# Schematic_final.net
KiCad netlist of a schematic drawn in EAGLE
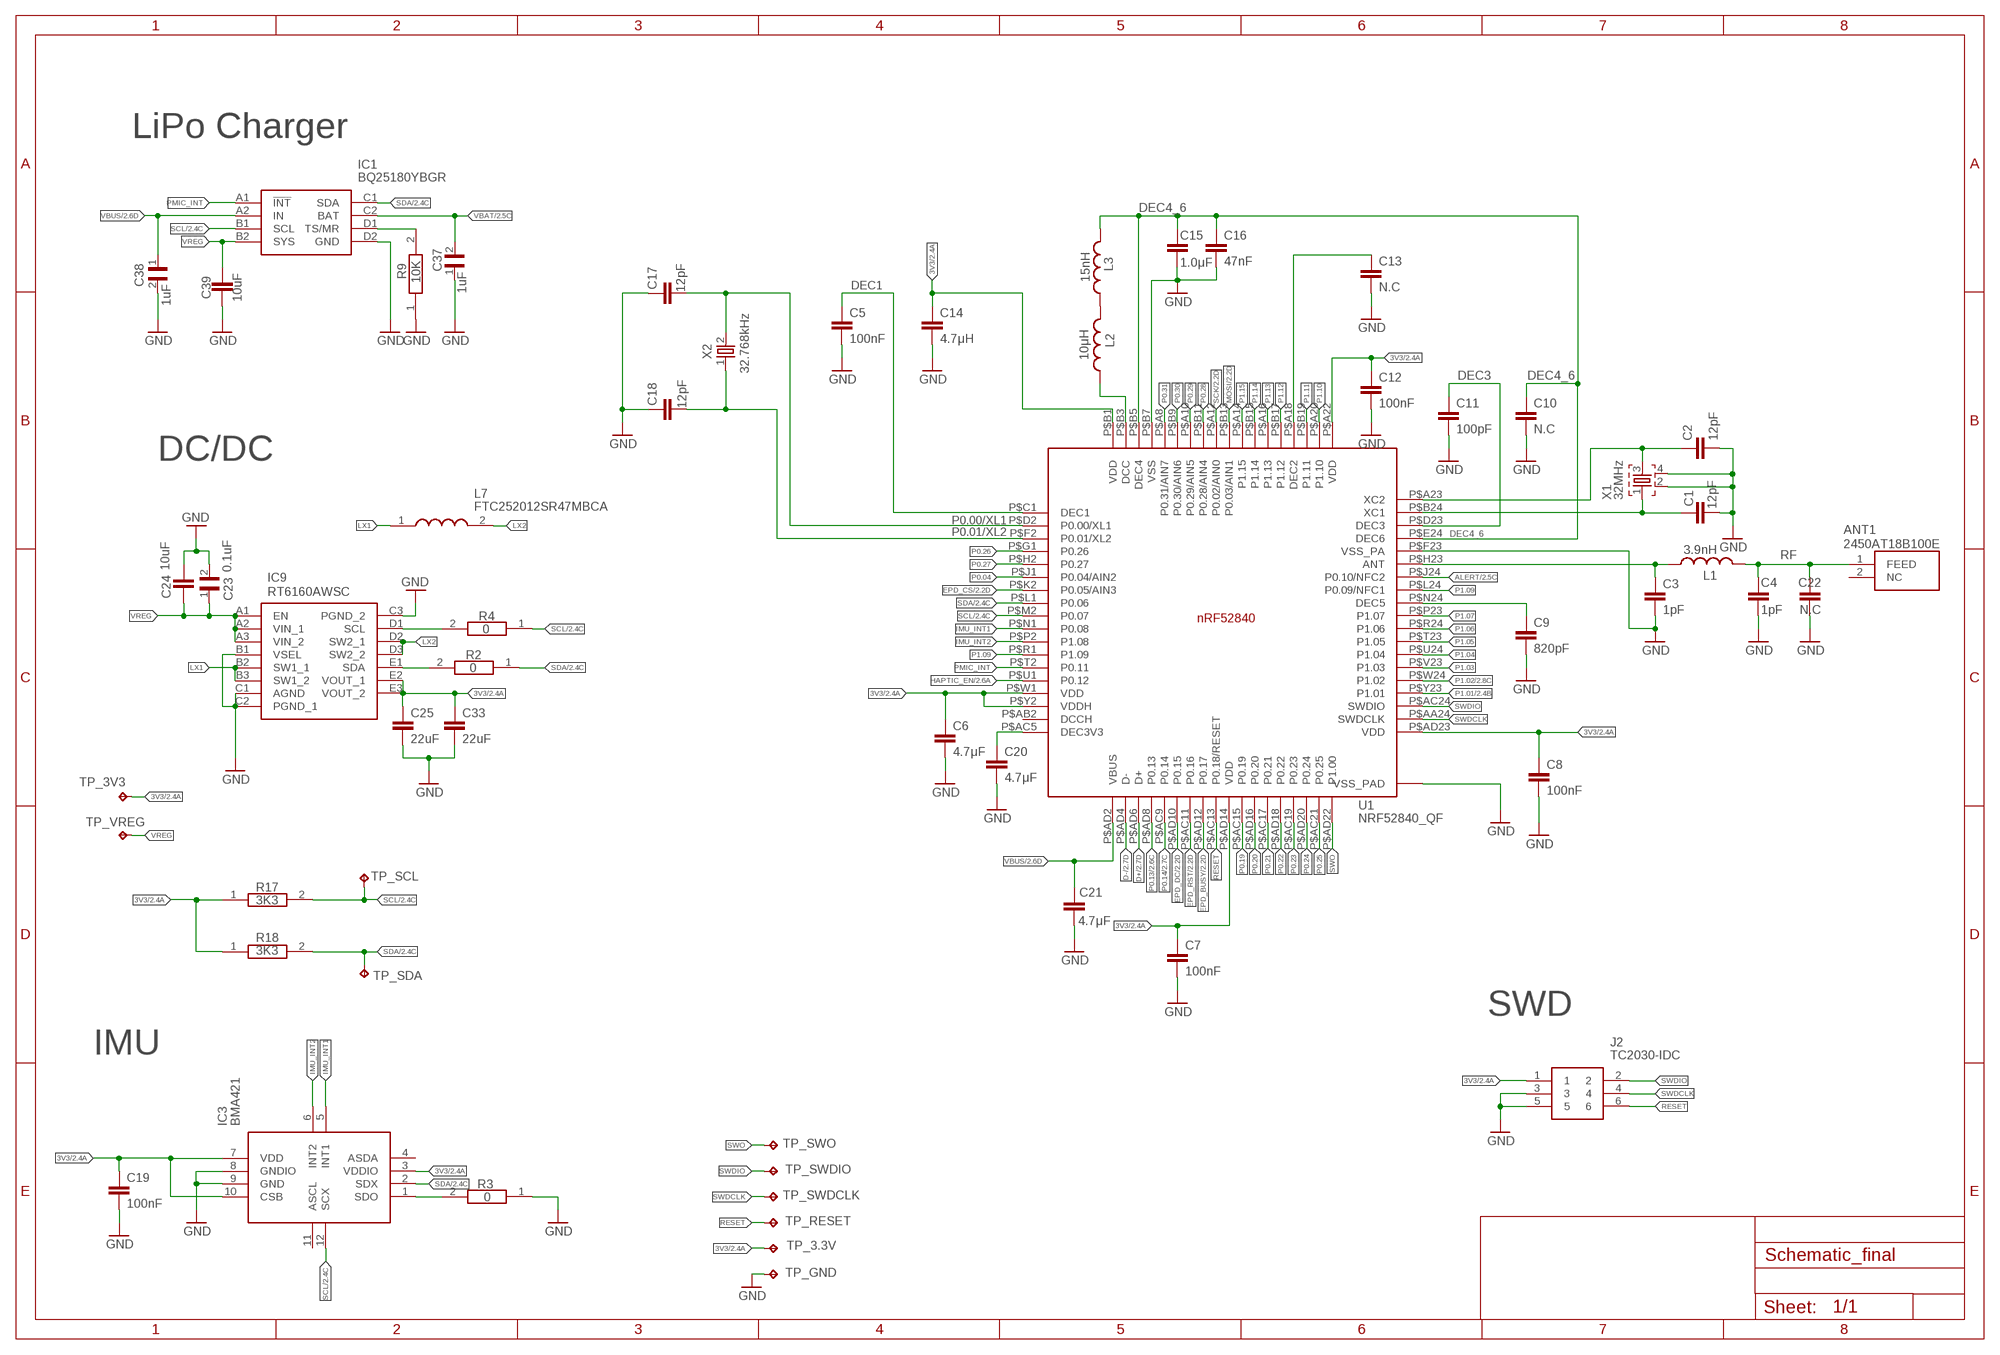
[diagram p0: schematic, sheet 1, part 1 of 2]
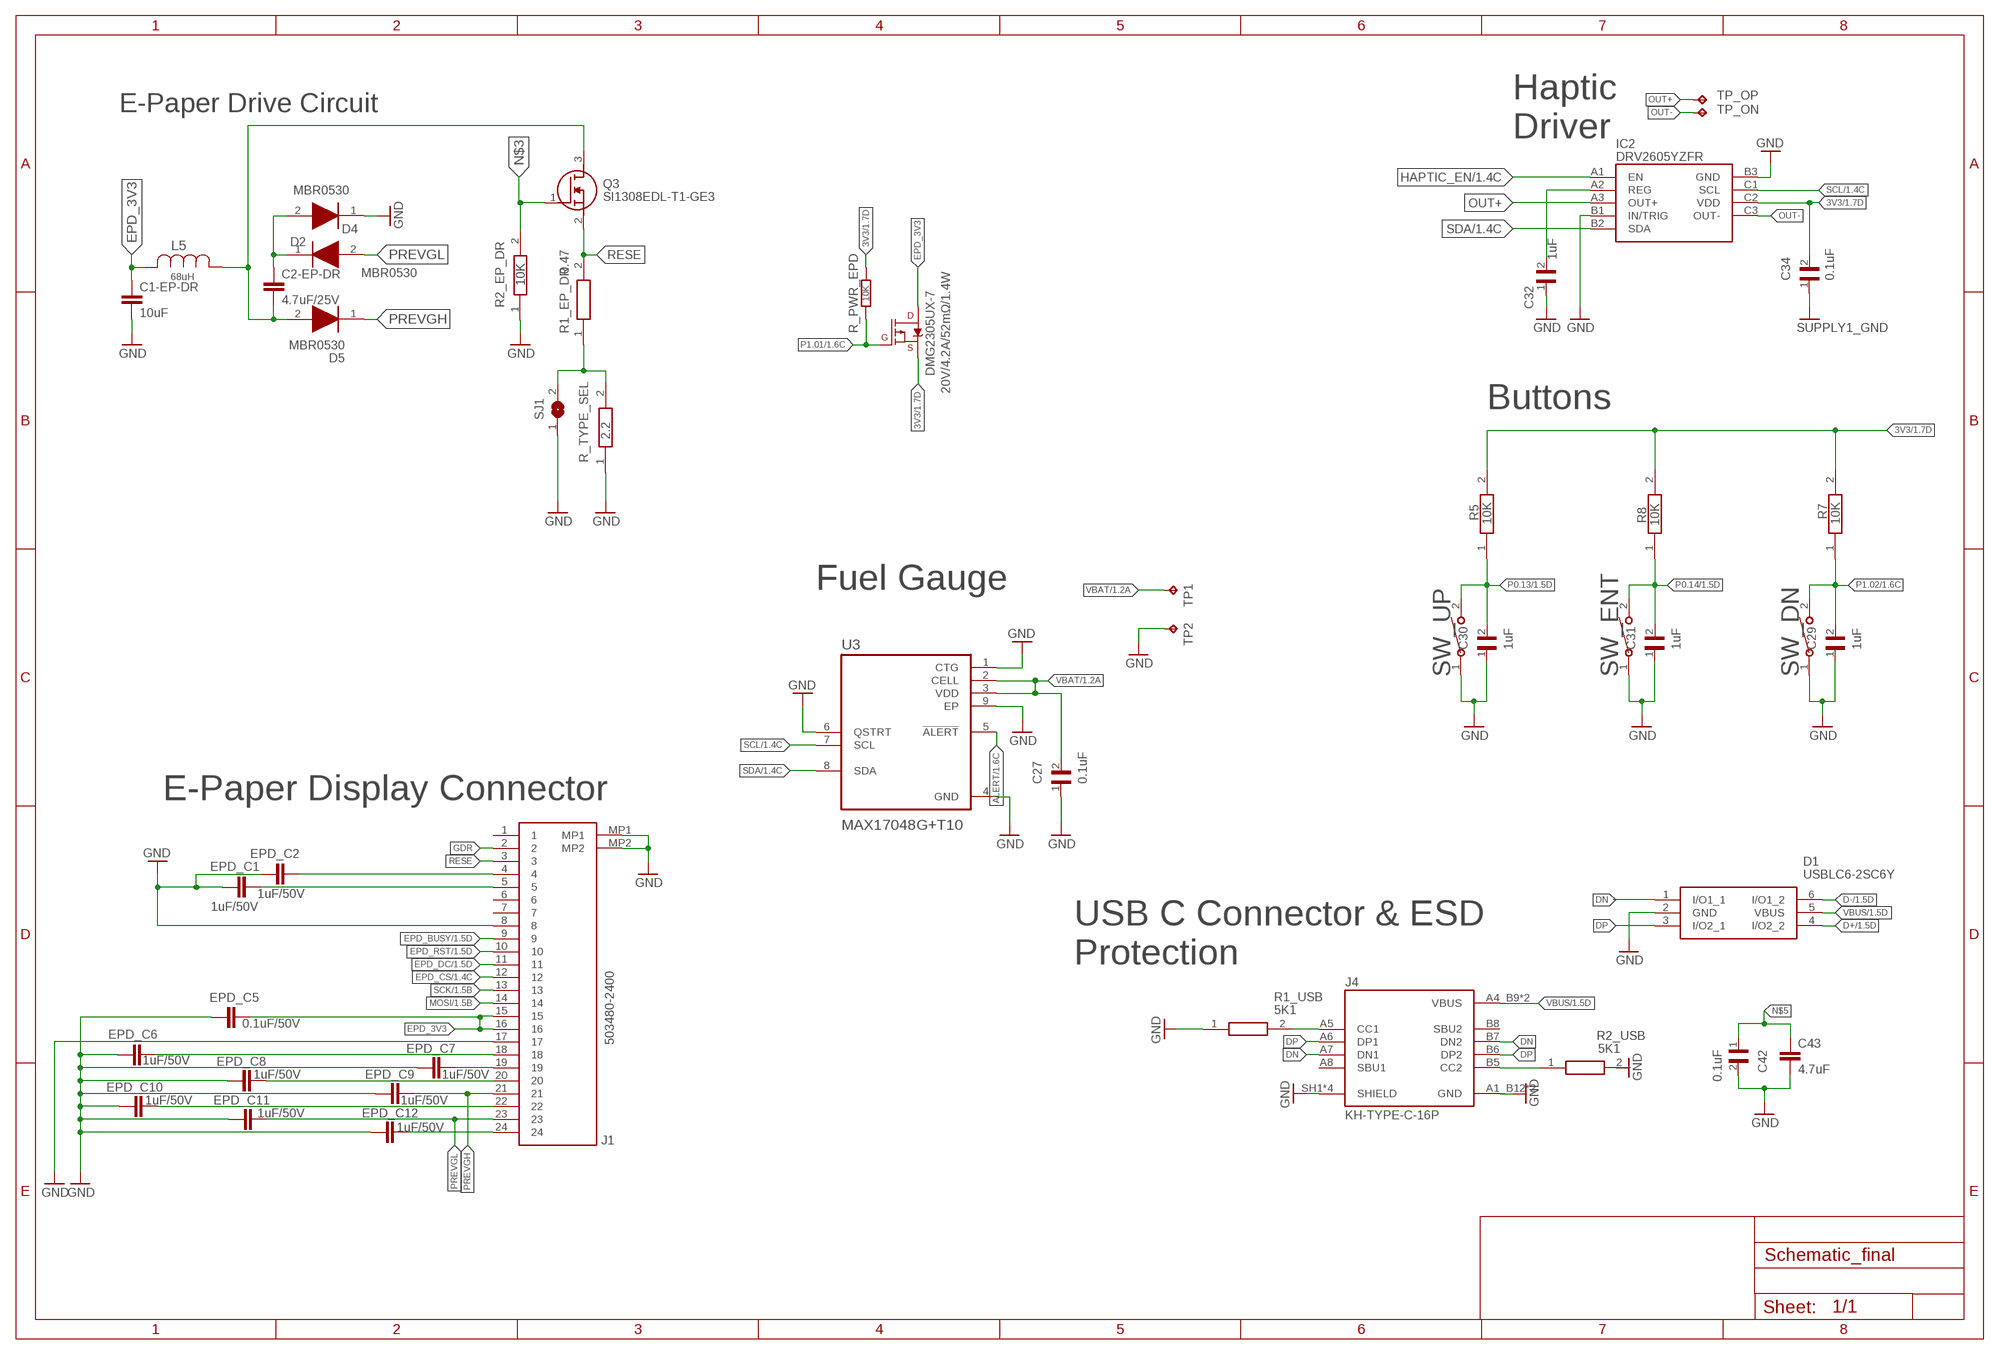
[diagram p1: schematic, sheet 1, part 2 of 2]

(export (version "E")
  (design (tool "Eeschema 10.0.6"))
  (components
    (comp (ref "ANT1")
      (value "2450AT18B100E")
      (footprint "eagle-import:2450AT18B100E_ANTC3216X140N")
      (fields (field (name "MOUSER_PART_NUMBER") "609-2450AT18B100E"))
      (libsource (lib "eagle-import") (part "2450AT18B100E_2450AT18B100E"))
    )
    (comp (ref "C1")
      (value "12pF")
      (footprint "eagle-import:NORDIC_NRF_3_RESC0201_L")
      (libsource (lib "eagle-import") (part "NORDIC_NRF_3_CAPACITOR_0201_L"))
    )
    (comp (ref "C1-EP-DR")
      (value "10uF")
      (footprint "eagle-import:NORDIC_NRF_3_RESC0201_L")
      (libsource (lib "eagle-import") (part "NORDIC_NRF_3_CAPACITOR_0201_L"))
    )
    (comp (ref "C2")
      (value "12pF")
      (footprint "eagle-import:NORDIC_NRF_3_RESC0201_L")
      (libsource (lib "eagle-import") (part "NORDIC_NRF_3_CAPACITOR_0201_L"))
    )
    (comp (ref "C2-EP-DR")
      (value "4.7uF/25V")
      (footprint "eagle-import:NORDIC_NRF_3_RESC0201_L")
      (libsource (lib "eagle-import") (part "NORDIC_NRF_3_CAPACITOR_0201_L"))
    )
    (comp (ref "C3")
      (value "1pF")
      (footprint "eagle-import:NORDIC_NRF_3_RESC0201_L")
      (libsource (lib "eagle-import") (part "NORDIC_NRF_3_CAPACITOR_0201_L"))
    )
    (comp (ref "C4")
      (value "1pF")
      (footprint "eagle-import:NORDIC_NRF_3_RESC0201_L")
      (libsource (lib "eagle-import") (part "NORDIC_NRF_3_CAPACITOR_0201_L"))
    )
    (comp (ref "C5")
      (value "100nF")
      (footprint "eagle-import:NORDIC_NRF_3_RESC0201_L")
      (libsource (lib "eagle-import") (part "NORDIC_NRF_3_CAPACITOR_0201_L"))
    )
    (comp (ref "C6")
      (value "4.7μF")
      (footprint "eagle-import:NORDIC_NRF_3_RESC0201_L")
      (libsource (lib "eagle-import") (part "NORDIC_NRF_3_CAPACITOR_0201_L"))
    )
    (comp (ref "C7")
      (value "100nF")
      (footprint "eagle-import:NORDIC_NRF_3_RESC0201_L")
      (libsource (lib "eagle-import") (part "NORDIC_NRF_3_CAPACITOR_0201_L"))
    )
    (comp (ref "C8")
      (value "100nF")
      (footprint "eagle-import:NORDIC_NRF_3_RESC0201_L")
      (libsource (lib "eagle-import") (part "NORDIC_NRF_3_CAPACITOR_0201_L"))
    )
    (comp (ref "C9")
      (value "820pF")
      (footprint "eagle-import:NORDIC_NRF_3_RESC0201_L")
      (libsource (lib "eagle-import") (part "NORDIC_NRF_3_CAPACITOR_0201_L"))
    )
    (comp (ref "C10")
      (value "N.C")
      (footprint "eagle-import:NORDIC_NRF_3_RESC0201_L")
      (libsource (lib "eagle-import") (part "NORDIC_NRF_3_CAPACITOR_0201_L"))
    )
    (comp (ref "C11")
      (value "100pF")
      (footprint "eagle-import:NORDIC_NRF_3_RESC0201_L")
      (libsource (lib "eagle-import") (part "NORDIC_NRF_3_CAPACITOR_0201_L"))
    )
    (comp (ref "C12")
      (value "100nF")
      (footprint "eagle-import:NORDIC_NRF_3_RESC0201_L")
      (libsource (lib "eagle-import") (part "NORDIC_NRF_3_CAPACITOR_0201_L"))
    )
    (comp (ref "C13")
      (value "N.C")
      (footprint "eagle-import:NORDIC_NRF_3_RESC0201_L")
      (libsource (lib "eagle-import") (part "NORDIC_NRF_3_CAPACITOR_0201_L"))
    )
    (comp (ref "C14")
      (value "4.7μH")
      (footprint "eagle-import:NORDIC_NRF_3_RESC0201_L")
      (libsource (lib "eagle-import") (part "NORDIC_NRF_3_CAPACITOR_0201_L"))
    )
    (comp (ref "C15")
      (value "1.0μF")
      (footprint "eagle-import:NORDIC_NRF_3_RESC0201_L")
      (libsource (lib "eagle-import") (part "NORDIC_NRF_3_CAPACITOR_0201_L"))
    )
    (comp (ref "C16")
      (value "47nF")
      (footprint "eagle-import:NORDIC_NRF_3_RESC0201_L")
      (libsource (lib "eagle-import") (part "NORDIC_NRF_3_CAPACITOR_0201_L"))
    )
    (comp (ref "C17")
      (value "12pF")
      (footprint "eagle-import:NORDIC_NRF_3_RESC0201_L")
      (libsource (lib "eagle-import") (part "NORDIC_NRF_3_CAPACITOR_0201_L"))
    )
    (comp (ref "C18")
      (value "12pF")
      (footprint "eagle-import:NORDIC_NRF_3_RESC0201_L")
      (libsource (lib "eagle-import") (part "NORDIC_NRF_3_CAPACITOR_0201_L"))
    )
    (comp (ref "C19")
      (value "100nF")
      (footprint "eagle-import:NORDIC_NRF_3_RESC0201_L")
      (libsource (lib "eagle-import") (part "NORDIC_NRF_3_CAPACITOR_0201_L"))
    )
    (comp (ref "C20")
      (value "4.7μF")
      (footprint "eagle-import:NORDIC_NRF_3_RESC0201_L")
      (libsource (lib "eagle-import") (part "NORDIC_NRF_3_CAPACITOR_0201_L"))
    )
    (comp (ref "C21")
      (value "4.7μF")
      (footprint "eagle-import:NORDIC_NRF_3_RESC0201_L")
      (libsource (lib "eagle-import") (part "NORDIC_NRF_3_CAPACITOR_0201_L"))
    )
    (comp (ref "C22")
      (value "N.C")
      (footprint "eagle-import:NORDIC_NRF_3_RESC0201_L")
      (libsource (lib "eagle-import") (part "NORDIC_NRF_3_CAPACITOR_0201_L"))
    )
    (comp (ref "C23")
      (value "0.1uF")
      (footprint "eagle-import:GRM011R60J152KE01L_2_CAPC0201X13N")
      (fields (field (name "MF") "Murata") (field (name "MP") "GRM011R60J152KE01L"))
      (libsource (lib "eagle-import") (part "GRM011R60J152KE01L_2_GRM011R60J152KE01L"))
    )
    (comp (ref "C24")
      (value "10uF")
      (footprint "eagle-import:NORDIC_NRF_3_RESC0201_L")
      (libsource (lib "eagle-import") (part "NORDIC_NRF_3_CAPACITOR_0201_L"))
    )
    (comp (ref "C25")
      (value "22uF")
      (footprint "eagle-import:NORDIC_NRF_3_RESC0201_L")
      (libsource (lib "eagle-import") (part "NORDIC_NRF_3_CAPACITOR_0201_L"))
    )
    (comp (ref "C27")
      (value "0.1uF")
      (footprint "eagle-import:GRM011R60J152KE01L_2_CAPC0201X13N")
      (fields (field (name "MF") "Murata") (field (name "MP") "GRM011R60J152KE01L"))
      (libsource (lib "eagle-import") (part "GRM011R60J152KE01L_2_GRM011R60J152KE01L"))
    )
    (comp (ref "C29")
      (value "1uF")
      (footprint "eagle-import:GRM011R60J152KE01L_2_CAPC0201X13N")
      (fields (field (name "MF") "Murata") (field (name "MP") "GRM011R60J152KE01L"))
      (libsource (lib "eagle-import") (part "GRM011R60J152KE01L_2_GRM011R60J152KE01L"))
    )
    (comp (ref "C30")
      (value "1uF")
      (footprint "eagle-import:GRM011R60J152KE01L_2_CAPC0201X13N")
      (fields (field (name "MF") "Murata") (field (name "MP") "GRM011R60J152KE01L"))
      (libsource (lib "eagle-import") (part "GRM011R60J152KE01L_2_GRM011R60J152KE01L"))
    )
    (comp (ref "C31")
      (value "1uF")
      (footprint "eagle-import:GRM011R60J152KE01L_2_CAPC0201X13N")
      (fields (field (name "MF") "Murata") (field (name "MP") "GRM011R60J152KE01L"))
      (libsource (lib "eagle-import") (part "GRM011R60J152KE01L_2_GRM011R60J152KE01L"))
    )
    (comp (ref "C32")
      (value "1uF")
      (footprint "eagle-import:GRM011R60J152KE01L_2_CAPC0201X13N")
      (fields (field (name "MF") "Murata") (field (name "MP") "GRM011R60J152KE01L"))
      (libsource (lib "eagle-import") (part "GRM011R60J152KE01L_2_GRM011R60J152KE01L"))
    )
    (comp (ref "C33")
      (value "22uF")
      (footprint "eagle-import:NORDIC_NRF_3_RESC0201_L")
      (libsource (lib "eagle-import") (part "NORDIC_NRF_3_CAPACITOR_0201_L"))
    )
    (comp (ref "C34")
      (value "0.1uF")
      (footprint "eagle-import:GRM011R60J152KE01L_2_CAPC0201X13N")
      (fields (field (name "MF") "Murata") (field (name "MP") "GRM011R60J152KE01L"))
      (libsource (lib "eagle-import") (part "GRM011R60J152KE01L_2_GRM011R60J152KE01L"))
    )
    (comp (ref "C37")
      (value "1uF")
      (footprint "eagle-import:GRM011R60J152KE01L_2_CAPC0201X13N")
      (fields (field (name "MF") "Murata") (field (name "MP") "GRM011R60J152KE01L"))
      (libsource (lib "eagle-import") (part "GRM011R60J152KE01L_2_GRM011R60J152KE01L"))
    )
    (comp (ref "C38")
      (value "1uF")
      (footprint "eagle-import:GRM011R60J152KE01L_2_CAPC0201X13N")
      (fields (field (name "MF") "Murata") (field (name "MP") "GRM011R60J152KE01L"))
      (libsource (lib "eagle-import") (part "GRM011R60J152KE01L_2_GRM011R60J152KE01L"))
    )
    (comp (ref "C39")
      (value "10uF")
      (footprint "eagle-import:NORDIC_NRF_3_RESC0201_L")
      (libsource (lib "eagle-import") (part "NORDIC_NRF_3_CAPACITOR_0201_L"))
    )
    (comp (ref "C42")
      (value "0.1uF")
      (footprint "eagle-import:GRM011R60J152KE01L_2_CAPC0201X13N")
      (fields (field (name "MF") "Murata") (field (name "MP") "GRM011R60J152KE01L"))
      (libsource (lib "eagle-import") (part "GRM011R60J152KE01L_2_GRM011R60J152KE01L"))
    )
    (comp (ref "C43")
      (value "4.7uF")
      (footprint "eagle-import:NORDIC_NRF_3_RESC0201_L")
      (libsource (lib "eagle-import") (part "NORDIC_NRF_3_CAPACITOR_0201_L"))
    )
    (comp (ref "D1")
      (value "USBLC6-2SC6Y")
      (footprint "eagle-import:ESP32_C6_LIBRARY_3_SOT95P280X145-6N")
      (fields (field (name "MF") "STMicroelectronics"))
      (libsource (lib "eagle-import") (part "ESP32_C6_LIBRARY_3_USBLC6-2SC6Y"))
    )
    (comp (ref "D2")
      (value "MBR0530")
      (footprint "eagle-import:ESP32_C6_LIBRARY_5_SOD3716X135N")
      (fields (field (name "MF") "ON Semiconductor"))
      (libsource (lib "eagle-import") (part "ESP32_C6_LIBRARY_5_MBR0530"))
    )
    (comp (ref "D4")
      (value "MBR0530")
      (footprint "eagle-import:ESP32_C6_LIBRARY_5_SOD3716X135N")
      (fields (field (name "MF") "ON Semiconductor"))
      (libsource (lib "eagle-import") (part "ESP32_C6_LIBRARY_5_MBR0530"))
    )
    (comp (ref "D5")
      (value "MBR0530")
      (footprint "eagle-import:ESP32_C6_LIBRARY_5_SOD3716X135N")
      (fields (field (name "MF") "ON Semiconductor"))
      (libsource (lib "eagle-import") (part "ESP32_C6_LIBRARY_5_MBR0530"))
    )
    (comp (ref "DMG2305UX-7")
      (value "20V/4.2A/52mΩ/1.4W")
      (footprint "eagle-import:ESP32_C6_LIBRARY_4_ESP32_C6_LIBRARY_4_ESP32_C6_LIBRARY_4_ESP32_C6_LIBRARY_4_ESP32_WROVER_SPARKFUN-DISCRETESEMI_SOT23-3")
      (libsource (lib "eagle-import") (part "ESP32_C6_LIBRARY_4_ESP32_WROVER_SPARKFUN-DISCRETESEMI_MOSFET_PCH-DMG2305UX-7"))
    )
    (comp (ref "EPD_C1")
      (value "1uF/50V")
      (footprint "eagle-import:NORDIC_NRF_3_RESC0201_L")
      (libsource (lib "eagle-import") (part "NORDIC_NRF_3_CAPACITOR_0201_L"))
    )
    (comp (ref "EPD_C2")
      (value "1uF/50V")
      (footprint "eagle-import:NORDIC_NRF_3_RESC0201_L")
      (libsource (lib "eagle-import") (part "NORDIC_NRF_3_CAPACITOR_0201_L"))
    )
    (comp (ref "EPD_C5")
      (value "0.1uF/50V")
      (footprint "eagle-import:NORDIC_NRF_3_RESC0201_L")
      (libsource (lib "eagle-import") (part "NORDIC_NRF_3_CAPACITOR_0201_L"))
    )
    (comp (ref "EPD_C6")
      (value "1uF/50V")
      (footprint "eagle-import:NORDIC_NRF_3_RESC0201_L")
      (libsource (lib "eagle-import") (part "NORDIC_NRF_3_CAPACITOR_0201_L"))
    )
    (comp (ref "EPD_C7")
      (value "1uF/50V")
      (footprint "eagle-import:NORDIC_NRF_3_RESC0201_L")
      (libsource (lib "eagle-import") (part "NORDIC_NRF_3_CAPACITOR_0201_L"))
    )
    (comp (ref "EPD_C8")
      (value "1uF/50V")
      (footprint "eagle-import:NORDIC_NRF_3_RESC0201_L")
      (libsource (lib "eagle-import") (part "NORDIC_NRF_3_CAPACITOR_0201_L"))
    )
    (comp (ref "EPD_C9")
      (value "1uF/50V")
      (footprint "eagle-import:NORDIC_NRF_3_RESC0201_L")
      (libsource (lib "eagle-import") (part "NORDIC_NRF_3_CAPACITOR_0201_L"))
    )
    (comp (ref "EPD_C10")
      (value "1uF/50V")
      (footprint "eagle-import:NORDIC_NRF_3_RESC0201_L")
      (libsource (lib "eagle-import") (part "NORDIC_NRF_3_CAPACITOR_0201_L"))
    )
    (comp (ref "EPD_C11")
      (value "1uF/50V")
      (footprint "eagle-import:NORDIC_NRF_3_RESC0201_L")
      (libsource (lib "eagle-import") (part "NORDIC_NRF_3_CAPACITOR_0201_L"))
    )
    (comp (ref "EPD_C12")
      (value "1uF/50V")
      (footprint "eagle-import:NORDIC_NRF_3_RESC0201_L")
      (libsource (lib "eagle-import") (part "NORDIC_NRF_3_CAPACITOR_0201_L"))
    )
    (comp (ref "IC1")
      (value "BQ25180YBGR")
      (footprint "eagle-import:BQ25180YBGR_BGA8C40P2X4_100X155X50")
      (fields (field (name "MOUSER_PART_NUMBER") "595-BQ25180YBGR"))
      (libsource (lib "eagle-import") (part "BQ25180YBGR_BQ25180YBGR"))
    )
    (comp (ref "IC2")
      (value "DRV2605YZFR")
      (footprint "eagle-import:DRV2605YZFR_BGA9C50P3X3_144X144X62")
      (libsource (lib "eagle-import") (part "DRV2605YZFR_DRV2605YZFR"))
    )
    (comp (ref "IC3")
      (value "BMA421")
      (footprint "eagle-import:BMA423_BMA423")
      (fields
        (field (name "MANUFACTURER_PART_NUMBER") "BMA423")
        (field (name "MOUSER_PART_NUMBER") "262-BMA423")
      )
      (libsource (lib "eagle-import") (part "BMA423_BMA423"))
    )
    (comp (ref "IC9")
      (value "RT6160AWSC")
      (footprint "eagle-import:RT6160AWSC_BGA15C40P3X5_140X230X60")
      (fields (field (name "MOUSER_PART_NUMBER") "835-RT6160AWSC"))
      (libsource (lib "eagle-import") (part "RT6160AWSC_RT6160AWSC"))
    )
    (comp (ref "J1")
      (value "503480-2400")
      (footprint "eagle-import:503480-2400_5034802400")
      (fields (field (name "MOUSER_PART_NUMBER") "538-503480-2400"))
      (libsource (lib "eagle-import") (part "503480-2400_503480-2400"))
    )
    (comp (ref "J2")
      (value "TC2030-IDC")
      (footprint "eagle-import:TC2030-IDC_TC2030IDC")
      (libsource (lib "eagle-import") (part "TC2030-IDC_TC2030-IDC"))
    )
    (comp (ref "J4")
      (value "KH-TYPE-C-16P")
      (footprint "eagle-import:KH-TYPE-C-16P_KINGHELM_KH-TYPE-C-16P")
      (fields (field (name "MF") "kinghelm"))
      (libsource (lib "eagle-import") (part "KH-TYPE-C-16P_KH-TYPE-C-16P"))
    )
    (comp (ref "L1")
      (value "3.9nH")
      (footprint "eagle-import:NORDIC_NRF_2_RESC0402_L")
      (libsource (lib "eagle-import") (part "NORDIC_NRF_2_INDUCTOR_0402_L"))
    )
    (comp (ref "L2")
      (value "10μH")
      (footprint "eagle-import:NORDIC_NRF_2_RESC0402_L")
      (libsource (lib "eagle-import") (part "NORDIC_NRF_2_INDUCTOR_0402_L"))
    )
    (comp (ref "L3")
      (value "15nH")
      (footprint "eagle-import:NORDIC_NRF_2_RESC0402_L")
      (libsource (lib "eagle-import") (part "NORDIC_NRF_2_INDUCTOR_0402_L"))
    )
    (comp (ref "L5")
      (value "68uH")
      (footprint "eagle-import:ESP32_C6_LIBRARY_2_IND_4828-WE-TPC_WRE")
      (fields
        (field (name "MANUFACTURER_PART_NUMBER") "744043680")
        (field (name "COPYRIGHT") "Copyright (C) 2024 Ultra Librarian. All rights reserved.")
      )
      (libsource (lib "eagle-import") (part "ESP32_C6_LIBRARY_2_744043680IND_4828-WE-TPC_WRE"))
    )
    (comp (ref "L7")
      (value "FTC252012SR47MBCA")
      (footprint "eagle-import:MLP2016SR47MT0S1_INDC2016X100N")
      (libsource (lib "eagle-import") (part "MLP2016SR47MT0S1_FTC252012SR47MBCA"))
    )
    (comp (ref "Q3")
      (value "SI1308EDL-T1-GE3")
      (footprint "eagle-import:ESP32_C6_LIBRARY_6_SOT65P210X110-3N")
      (fields (field (name "MF") "Vishay Siliconix"))
      (libsource (lib "eagle-import") (part "ESP32_C6_LIBRARY_6_SI1308EDL-T1-GE3"))
    )
    (comp (ref "R1_EP_DR")
      (value "0.47")
      (footprint "eagle-import:CPF0201D7K68C1_0201")
      (libsource (lib "eagle-import") (part "CPF0201D7K68C1_CPF0201D7K68C1"))
    )
    (comp (ref "R1_USB")
      (value "5K1")
      (footprint "eagle-import:CPF0201D7K68C1_0201")
      (libsource (lib "eagle-import") (part "CPF0201D7K68C1_CPF0201D7K68C1"))
    )
    (comp (ref "R2")
      (value "0")
      (footprint "eagle-import:CPF0201D7K68C1_0201")
      (libsource (lib "eagle-import") (part "CPF0201D7K68C1_CPF0201D7K68C1"))
    )
    (comp (ref "R2_EP_DR")
      (value "10K")
      (footprint "eagle-import:CPF0201D7K68C1_0201")
      (libsource (lib "eagle-import") (part "CPF0201D7K68C1_CPF0201D7K68C1"))
    )
    (comp (ref "R2_USB")
      (value "5K1")
      (footprint "eagle-import:CPF0201D7K68C1_0201")
      (libsource (lib "eagle-import") (part "CPF0201D7K68C1_CPF0201D7K68C1"))
    )
    (comp (ref "R3")
      (value "0")
      (footprint "eagle-import:CPF0201D7K68C1_0201")
      (libsource (lib "eagle-import") (part "CPF0201D7K68C1_CPF0201D7K68C1"))
    )
    (comp (ref "R4")
      (value "0")
      (footprint "eagle-import:CPF0201D7K68C1_0201")
      (libsource (lib "eagle-import") (part "CPF0201D7K68C1_CPF0201D7K68C1"))
    )
    (comp (ref "R5")
      (value "10K")
      (footprint "eagle-import:CPF0201D7K68C1_0201")
      (libsource (lib "eagle-import") (part "CPF0201D7K68C1_CPF0201D7K68C1"))
    )
    (comp (ref "R7")
      (value "10K")
      (footprint "eagle-import:CPF0201D7K68C1_0201")
      (libsource (lib "eagle-import") (part "CPF0201D7K68C1_CPF0201D7K68C1"))
    )
    (comp (ref "R8")
      (value "10K")
      (footprint "eagle-import:CPF0201D7K68C1_0201")
      (libsource (lib "eagle-import") (part "CPF0201D7K68C1_CPF0201D7K68C1"))
    )
    (comp (ref "R9")
      (value "10K")
      (footprint "eagle-import:CPF0201D7K68C1_0201")
      (libsource (lib "eagle-import") (part "CPF0201D7K68C1_CPF0201D7K68C1"))
    )
    (comp (ref "R17")
      (value "3K3")
      (footprint "eagle-import:CPF0201D7K68C1_0201")
      (libsource (lib "eagle-import") (part "CPF0201D7K68C1_CPF0201D7K68C1"))
    )
    (comp (ref "R18")
      (value "3K3")
      (footprint "eagle-import:CPF0201D7K68C1_0201")
      (libsource (lib "eagle-import") (part "CPF0201D7K68C1_CPF0201D7K68C1"))
    )
    (comp (ref "R_PWR_EPD")
      (value "10K")
      (footprint "eagle-import:RESC1005X40")
      (libsource (lib "eagle-import") (part "RESISTOR_CHIP-0402(1005-METRIC)_"))
    )
    (comp (ref "R_TYPE_SEL")
      (value "2.2")
      (footprint "eagle-import:CPF0201D7K68C1_0201")
      (libsource (lib "eagle-import") (part "CPF0201D7K68C1_CPF0201D7K68C1"))
    )
    (comp (ref "SJ1")
      (value "ESP32_C6_LIBRARY_7_JUMPER_SJ")
      (footprint "eagle-import:ESP32_C6_LIBRARY_7_JUMPER_SJ")
      (libsource (lib "eagle-import") (part "ESP32_C6_LIBRARY_7_JUMPER_SJ"))
    )
    (comp (ref "SW_DN")
      (value "2025-10-22_07-23-44_LIBRARY_EVP-AKE31ASW_EVP-AKE31A_PAN")
      (footprint "eagle-import:2025-10-22_07-23-44_LIBRARY_SW_EVP-AKE31A_PAN")
      (fields
        (field (name "MANUFACTURER_PART_NUMBER") "EVP-AKE31A")
        (field (name "COPYRIGHT") "Copyright (C) 2025 Ultra Librarian. All rights reserved.")
      )
      (libsource (lib "eagle-import") (part "2025-10-22_07-23-44_LIBRARY_EVP-AKE31ASW_EVP-AKE31A_PAN"))
    )
    (comp (ref "SW_ENT")
      (value "2025-10-22_07-23-44_LIBRARY_EVP-AKE31ASW_EVP-AKE31A_PAN")
      (footprint "eagle-import:2025-10-22_07-23-44_LIBRARY_SW_EVP-AKE31A_PAN")
      (fields
        (field (name "MANUFACTURER_PART_NUMBER") "EVP-AKE31A")
        (field (name "COPYRIGHT") "Copyright (C) 2025 Ultra Librarian. All rights reserved.")
      )
      (libsource (lib "eagle-import") (part "2025-10-22_07-23-44_LIBRARY_EVP-AKE31ASW_EVP-AKE31A_PAN"))
    )
    (comp (ref "SW_UP")
      (value "2025-10-22_07-23-44_LIBRARY_EVP-AKE31ASW_EVP-AKE31A_PAN")
      (footprint "eagle-import:2025-10-22_07-23-44_LIBRARY_SW_EVP-AKE31A_PAN")
      (fields
        (field (name "MANUFACTURER_PART_NUMBER") "EVP-AKE31A")
        (field (name "COPYRIGHT") "Copyright (C) 2025 Ultra Librarian. All rights reserved.")
      )
      (libsource (lib "eagle-import") (part "2025-10-22_07-23-44_LIBRARY_EVP-AKE31ASW_EVP-AKE31A_PAN"))
    )
    (comp (ref "TP1")
      (value "HECTOR_WATCH_1_TPTP20R")
      (footprint "eagle-import:HECTOR_WATCH_1_TP20R")
      (libsource (lib "eagle-import") (part "HECTOR_WATCH_1_TPTP20R"))
    )
    (comp (ref "TP2")
      (value "HECTOR_WATCH_1_TPTP20R")
      (footprint "eagle-import:HECTOR_WATCH_1_TP20R")
      (libsource (lib "eagle-import") (part "HECTOR_WATCH_1_TPTP20R"))
    )
    (comp (ref "TP_3.3V")
      (value "HECTOR_WATCH_1_TPTP20R")
      (footprint "eagle-import:HECTOR_WATCH_1_TP20R")
      (libsource (lib "eagle-import") (part "HECTOR_WATCH_1_TPTP20R"))
    )
    (comp (ref "TP_3V3")
      (value "HECTOR_WATCH_1_TPTP20R")
      (footprint "eagle-import:HECTOR_WATCH_1_TP20R")
      (libsource (lib "eagle-import") (part "HECTOR_WATCH_1_TPTP20R"))
    )
    (comp (ref "TP_GND")
      (value "HECTOR_WATCH_1_TPTP20R")
      (footprint "eagle-import:HECTOR_WATCH_1_TP20R")
      (libsource (lib "eagle-import") (part "HECTOR_WATCH_1_TPTP20R"))
    )
    (comp (ref "TP_ON")
      (value "HECTOR_WATCH_1_TPTP20R")
      (footprint "eagle-import:HECTOR_WATCH_1_TP20R")
      (libsource (lib "eagle-import") (part "HECTOR_WATCH_1_TPTP20R"))
    )
    (comp (ref "TP_OP")
      (value "TP_OP")
      (footprint "eagle-import:HECTOR_WATCH_1_TP20R")
      (libsource (lib "eagle-import") (part "HECTOR_WATCH_1_TPTP20R"))
    )
    (comp (ref "TP_RESET")
      (value "HECTOR_WATCH_1_TPTP20R")
      (footprint "eagle-import:HECTOR_WATCH_1_TP20R")
      (libsource (lib "eagle-import") (part "HECTOR_WATCH_1_TPTP20R"))
    )
    (comp (ref "TP_SCL")
      (value "HECTOR_WATCH_1_TPTP20R")
      (footprint "eagle-import:HECTOR_WATCH_1_TP20R")
      (libsource (lib "eagle-import") (part "HECTOR_WATCH_1_TPTP20R"))
    )
    (comp (ref "TP_SDA")
      (value "HECTOR_WATCH_1_TPTP20R")
      (footprint "eagle-import:HECTOR_WATCH_1_TP20R")
      (libsource (lib "eagle-import") (part "HECTOR_WATCH_1_TPTP20R"))
    )
    (comp (ref "TP_SWDCLK")
      (value "HECTOR_WATCH_1_TPTP20R")
      (footprint "eagle-import:HECTOR_WATCH_1_TP20R")
      (libsource (lib "eagle-import") (part "HECTOR_WATCH_1_TPTP20R"))
    )
    (comp (ref "TP_SWDIO")
      (value "HECTOR_WATCH_1_TPTP20R")
      (footprint "eagle-import:HECTOR_WATCH_1_TP20R")
      (libsource (lib "eagle-import") (part "HECTOR_WATCH_1_TPTP20R"))
    )
    (comp (ref "TP_SWO")
      (value "HECTOR_WATCH_1_TPTP20R")
      (footprint "eagle-import:HECTOR_WATCH_1_TP20R")
      (libsource (lib "eagle-import") (part "HECTOR_WATCH_1_TPTP20R"))
    )
    (comp (ref "TP_VREG")
      (value "HECTOR_WATCH_1_TPTP20R")
      (footprint "eagle-import:HECTOR_WATCH_1_TP20R")
      (libsource (lib "eagle-import") (part "HECTOR_WATCH_1_TPTP20R"))
    )
    (comp (ref "U1")
      (value "NRF52840_QF")
      (footprint "eagle-import:NORDIC_NRF_4_AQFN50P700X700X85_HS-74N")
      (libsource (lib "eagle-import") (part "NORDIC_NRF_4_NRF52840_QF"))
    )
    (comp (ref "U3")
      (value "MAX17048G+T10")
      (footprint "eagle-import:ESP32_C6_LIBRARY_SON50P200X200X80-9N")
      (fields (field (name "MF") "Analog Devices"))
      (libsource (lib "eagle-import") (part "ESP32_C6_LIBRARY_MAX17048G+T10"))
    )
    (comp (ref "X1")
      (value "32MHz")
      (footprint "eagle-import:NORDIC_NRF_BT-XTAL_2016_N")
      (libsource (lib "eagle-import") (part "NORDIC_NRF_XTAL_32MHZ"))
    )
    (comp (ref "X2")
      (value "32.768kHz")
      (footprint "eagle-import:NORDIC_NRF_1_XTAL_3215_N")
      (libsource (lib "eagle-import") (part "NORDIC_NRF_1_XTAL_32KHZ"))
    )
  )
  (nets
    (net (code "1") (name "/DEC1") (class "Default")
      (node (ref "C5") (pin "1") (pinfunction "1_1") (pintype "passive"))
      (node (ref "U1") (pin "P$C1") (pinfunction "DEC1_P$C1") (pintype "power_in"))
    )
    (net (code "2") (name "/DEC3") (class "Default")
      (node (ref "C11") (pin "1") (pinfunction "1_1") (pintype "passive"))
      (node (ref "U1") (pin "P$D23") (pinfunction "DEC3_P$D23") (pintype "bidirectional"))
    )
    (net (code "3") (name "/DEC4_6") (class "Default")
      (node (ref "C10") (pin "1") (pinfunction "1_1") (pintype "passive"))
      (node (ref "C15") (pin "1") (pinfunction "1_1") (pintype "passive"))
      (node (ref "C16") (pin "1") (pinfunction "1_1") (pintype "passive"))
      (node (ref "L3") (pin "2") (pinfunction "2_2") (pintype "passive"))
      (node (ref "U1") (pin "P$B5") (pinfunction "DEC4_P$B5") (pintype "power_in"))
      (node (ref "U1") (pin "P$E24") (pinfunction "DEC6_P$E24") (pintype "bidirectional"))
    )
    (net (code "4") (name "/P0.00{slash}XL1") (class "Default")
      (node (ref "C17") (pin "2") (pinfunction "2_2") (pintype "passive"))
      (node (ref "U1") (pin "P$D2") (pinfunction "P0.00/XL1_P$D2") (pintype "bidirectional"))
      (node (ref "X2") (pin "2") (pinfunction "2_2") (pintype "passive"))
    )
    (net (code "5") (name "/P0.01{slash}XL2") (class "Default")
      (node (ref "C18") (pin "2") (pinfunction "2_2") (pintype "passive"))
      (node (ref "U1") (pin "P$F2") (pinfunction "P0.01/XL2_P$F2") (pintype "bidirectional"))
      (node (ref "X2") (pin "1") (pinfunction "1_1") (pintype "passive"))
    )
    (net (code "6") (name "/RF") (class "Default")
      (node (ref "ANT1") (pin "1") (pinfunction "FEED_1") (pintype "input"))
      (node (ref "C22") (pin "1") (pinfunction "1_1") (pintype "passive"))
      (node (ref "C4") (pin "1") (pinfunction "1_1") (pintype "passive"))
      (node (ref "L1") (pin "2") (pinfunction "2_2") (pintype "passive"))
    )
    (net (code "7") (name "3V3{slash}1.7D") (class "Default")
      (node (ref "C34") (pin "2") (pinfunction "2_2") (pintype "passive"))
      (node (ref "DMG2305UX-7") (pin "2") (pinfunction "S_2") (pintype "bidirectional"))
      (node (ref "IC2") (pin "C2") (pinfunction "VDD_C2") (pintype "bidirectional"))
      (node (ref "R5") (pin "2") (pinfunction "2_2") (pintype "bidirectional"))
      (node (ref "R7") (pin "2") (pinfunction "2_2") (pintype "bidirectional"))
      (node (ref "R8") (pin "2") (pinfunction "2_2") (pintype "bidirectional"))
      (node (ref "R_PWR_EPD") (pin "2") (pinfunction "2_2") (pintype "passive"))
    )
    (net (code "8") (name "3V3{slash}2.4A") (class "Default")
      (node (ref "C12") (pin "1") (pinfunction "1_1") (pintype "passive"))
      (node (ref "C14") (pin "1") (pinfunction "1_1") (pintype "passive"))
      (node (ref "C19") (pin "1") (pinfunction "1_1") (pintype "passive"))
      (node (ref "C25") (pin "1") (pinfunction "1_1") (pintype "passive"))
      (node (ref "C33") (pin "1") (pinfunction "1_1") (pintype "passive"))
      (node (ref "C6") (pin "1") (pinfunction "1_1") (pintype "passive"))
      (node (ref "C7") (pin "1") (pinfunction "1_1") (pintype "passive"))
      (node (ref "C8") (pin "1") (pinfunction "1_1") (pintype "passive"))
      (node (ref "IC3") (pin "10") (pinfunction "CSB_10") (pintype "bidirectional"))
      (node (ref "IC3") (pin "3") (pinfunction "VDDIO_3") (pintype "bidirectional"))
      (node (ref "IC3") (pin "7") (pinfunction "VDD_7") (pintype "bidirectional"))
      (node (ref "IC9") (pin "E2") (pinfunction "VOUT_1_E2") (pintype "bidirectional"))
      (node (ref "IC9") (pin "E3") (pinfunction "VOUT_2_E3") (pintype "bidirectional"))
      (node (ref "J2") (pin "1") (pinfunction "1_1") (pintype "bidirectional"))
      (node (ref "R17") (pin "1") (pinfunction "1_1") (pintype "bidirectional"))
      (node (ref "R18") (pin "1") (pinfunction "1_1") (pintype "bidirectional"))
      (node (ref "TP_3.3V") (pin "TP") (pinfunction "TP_TP") (pintype "input"))
      (node (ref "TP_3V3") (pin "TP") (pinfunction "TP_TP") (pintype "input"))
      (node (ref "U1") (pin "P$A22") (pinfunction "VDD_P$A22") (pintype "power_in"))
      (node (ref "U1") (pin "P$AD14") (pinfunction "VDD_P$AD14") (pintype "power_in"))
      (node (ref "U1") (pin "P$AD23") (pinfunction "VDD_P$AD23") (pintype "power_in"))
      (node (ref "U1") (pin "P$B1") (pinfunction "VDD_P$B1") (pintype "power_in"))
      (node (ref "U1") (pin "P$W1") (pinfunction "VDD_P$W1") (pintype "power_in"))
      (node (ref "U1") (pin "P$Y2") (pinfunction "VDDH_P$Y2") (pintype "power_in"))
    )
    (net (code "9") (name "ALERT{slash}1.6C") (class "Default")
      (node (ref "U3") (pin "5") (pinfunction "~{ALERT}_5") (pintype "output"))
    )
    (net (code "10") (name "ALERT{slash}2.5C") (class "Default")
      (node (ref "U1") (pin "P$J24") (pinfunction "P0.10/NFC2_P$J24") (pintype "bidirectional"))
    )
    (net (code "11") (name "D+{slash}1.5D") (class "Default")
      (node (ref "D1") (pin "4") (pinfunction "I/O2_2_4") (pintype "bidirectional"))
    )
    (net (code "12") (name "D+{slash}2.7D") (class "Default")
      (node (ref "U1") (pin "P$AD6") (pinfunction "D+_P$AD6") (pintype "bidirectional"))
    )
    (net (code "13") (name "D-{slash}1.5D") (class "Default")
      (node (ref "D1") (pin "6") (pinfunction "I/O1_2_6") (pintype "bidirectional"))
    )
    (net (code "14") (name "D-{slash}2.7D") (class "Default")
      (node (ref "U1") (pin "P$AD4") (pinfunction "D-_P$AD4") (pintype "bidirectional"))
    )
    (net (code "15") (name "DN") (class "Default")
      (node (ref "D1") (pin "1") (pinfunction "I/O1_1_1") (pintype "bidirectional"))
      (node (ref "J4") (pin "A7") (pinfunction "DN1_A7") (pintype "bidirectional"))
      (node (ref "J4") (pin "B7") (pinfunction "DN2_B7") (pintype "bidirectional"))
    )
    (net (code "16") (name "DP") (class "Default")
      (node (ref "D1") (pin "3") (pinfunction "I/O2_1_3") (pintype "bidirectional"))
      (node (ref "J4") (pin "A6") (pinfunction "DP1_A6") (pintype "bidirectional"))
      (node (ref "J4") (pin "B6") (pinfunction "DP2_B6") (pintype "bidirectional"))
    )
    (net (code "17") (name "EPD_3V3") (class "Default")
      (node (ref "C1-EP-DR") (pin "1") (pinfunction "1_1") (pintype "passive"))
      (node (ref "DMG2305UX-7") (pin "3") (pinfunction "D_3") (pintype "bidirectional"))
      (node (ref "EPD_C5") (pin "2") (pinfunction "2_2") (pintype "passive"))
      (node (ref "J1") (pin "15") (pinfunction "15_15") (pintype "bidirectional"))
      (node (ref "J1") (pin "16") (pinfunction "16_16") (pintype "bidirectional"))
      (node (ref "L5") (pin "2") (pinfunction "2_2") (pintype "passive"))
    )
    (net (code "18") (name "EPD_BUSY{slash}1.5D") (class "Default")
      (node (ref "J1") (pin "9") (pinfunction "9_9") (pintype "bidirectional"))
    )
    (net (code "19") (name "EPD_BUSY{slash}2.2D") (class "Default")
      (node (ref "U1") (pin "P$AD12") (pinfunction "P0.17_P$AD12") (pintype "bidirectional"))
    )
    (net (code "20") (name "EPD_CS{slash}1.4C") (class "Default")
      (node (ref "J1") (pin "12") (pinfunction "12_12") (pintype "bidirectional"))
    )
    (net (code "21") (name "EPD_CS{slash}2.2D") (class "Default")
      (node (ref "U1") (pin "P$K2") (pinfunction "P0.05/AIN3_P$K2") (pintype "bidirectional"))
    )
    (net (code "22") (name "EPD_DC{slash}1.5D") (class "Default")
      (node (ref "J1") (pin "11") (pinfunction "11_11") (pintype "bidirectional"))
    )
    (net (code "23") (name "EPD_DC{slash}2.2D") (class "Default")
      (node (ref "U1") (pin "P$AD10") (pinfunction "P0.15_P$AD10") (pintype "bidirectional"))
    )
    (net (code "24") (name "EPD_RST{slash}1.5D") (class "Default")
      (node (ref "J1") (pin "10") (pinfunction "10_10") (pintype "bidirectional"))
    )
    (net (code "25") (name "EPD_RST{slash}2.2D") (class "Default")
      (node (ref "U1") (pin "P$AC11") (pinfunction "P0.16_P$AC11") (pintype "bidirectional"))
    )
    (net (code "26") (name "GDR") (class "Default")
      (node (ref "J1") (pin "2") (pinfunction "2_2") (pintype "bidirectional"))
    )
    (net (code "27") (name "GND") (class "Default")
      (node (ref "C1") (pin "2") (pinfunction "2_2") (pintype "passive"))
      (node (ref "C1-EP-DR") (pin "2") (pinfunction "2_2") (pintype "passive"))
      (node (ref "C10") (pin "2") (pinfunction "2_2") (pintype "passive"))
      (node (ref "C11") (pin "2") (pinfunction "2_2") (pintype "passive"))
      (node (ref "C12") (pin "2") (pinfunction "2_2") (pintype "passive"))
      (node (ref "C13") (pin "2") (pinfunction "2_2") (pintype "passive"))
      (node (ref "C14") (pin "2") (pinfunction "2_2") (pintype "passive"))
      (node (ref "C15") (pin "2") (pinfunction "2_2") (pintype "passive"))
      (node (ref "C16") (pin "2") (pinfunction "2_2") (pintype "passive"))
      (node (ref "C17") (pin "1") (pinfunction "1_1") (pintype "passive"))
      (node (ref "C18") (pin "1") (pinfunction "1_1") (pintype "passive"))
      (node (ref "C19") (pin "2") (pinfunction "2_2") (pintype "passive"))
      (node (ref "C2") (pin "2") (pinfunction "2_2") (pintype "passive"))
      (node (ref "C20") (pin "2") (pinfunction "2_2") (pintype "passive"))
      (node (ref "C21") (pin "2") (pinfunction "2_2") (pintype "passive"))
      (node (ref "C22") (pin "2") (pinfunction "2_2") (pintype "passive"))
      (node (ref "C23") (pin "2") (pinfunction "2_2") (pintype "passive"))
      (node (ref "C24") (pin "1") (pinfunction "1_1") (pintype "passive"))
      (node (ref "C25") (pin "2") (pinfunction "2_2") (pintype "passive"))
      (node (ref "C27") (pin "1") (pinfunction "1_1") (pintype "passive"))
      (node (ref "C29") (pin "1") (pinfunction "1_1") (pintype "passive"))
      (node (ref "C3") (pin "2") (pinfunction "2_2") (pintype "passive"))
      (node (ref "C30") (pin "1") (pinfunction "1_1") (pintype "passive"))
      (node (ref "C31") (pin "1") (pinfunction "1_1") (pintype "passive"))
      (node (ref "C32") (pin "1") (pinfunction "1_1") (pintype "passive"))
      (node (ref "C33") (pin "2") (pinfunction "2_2") (pintype "passive"))
      (node (ref "C34") (pin "1") (pinfunction "1_1") (pintype "passive"))
      (node (ref "C37") (pin "1") (pinfunction "1_1") (pintype "passive"))
      (node (ref "C38") (pin "2") (pinfunction "2_2") (pintype "passive"))
      (node (ref "C39") (pin "2") (pinfunction "2_2") (pintype "passive"))
      (node (ref "C4") (pin "2") (pinfunction "2_2") (pintype "passive"))
      (node (ref "C42") (pin "2") (pinfunction "2_2") (pintype "passive"))
      (node (ref "C43") (pin "2") (pinfunction "2_2") (pintype "passive"))
      (node (ref "C5") (pin "2") (pinfunction "2_2") (pintype "passive"))
      (node (ref "C6") (pin "2") (pinfunction "2_2") (pintype "passive"))
      (node (ref "C7") (pin "2") (pinfunction "2_2") (pintype "passive"))
      (node (ref "C8") (pin "2") (pinfunction "2_2") (pintype "passive"))
      (node (ref "C9") (pin "2") (pinfunction "2_2") (pintype "passive"))
      (node (ref "D1") (pin "2") (pinfunction "GND_2") (pintype "bidirectional"))
      (node (ref "D4") (pin "1") (pinfunction "K_1") (pintype "bidirectional"))
      (node (ref "EPD_C1") (pin "1") (pinfunction "1_1") (pintype "passive"))
      (node (ref "EPD_C10") (pin "1") (pinfunction "1_1") (pintype "passive"))
      (node (ref "EPD_C11") (pin "1") (pinfunction "1_1") (pintype "passive"))
      (node (ref "EPD_C12") (pin "1") (pinfunction "1_1") (pintype "passive"))
      (node (ref "EPD_C2") (pin "1") (pinfunction "1_1") (pintype "passive"))
      (node (ref "EPD_C5") (pin "1") (pinfunction "1_1") (pintype "passive"))
      (node (ref "EPD_C6") (pin "1") (pinfunction "1_1") (pintype "passive"))
      (node (ref "EPD_C7") (pin "1") (pinfunction "1_1") (pintype "passive"))
      (node (ref "EPD_C8") (pin "1") (pinfunction "1_1") (pintype "passive"))
      (node (ref "EPD_C9") (pin "1") (pinfunction "1_1") (pintype "passive"))
      (node (ref "IC1") (pin "D2") (pinfunction "GND_D2") (pintype "bidirectional"))
      (node (ref "IC2") (pin "B1") (pinfunction "IN/TRIG_B1") (pintype "bidirectional"))
      (node (ref "IC2") (pin "B3") (pinfunction "GND_B3") (pintype "bidirectional"))
      (node (ref "IC3") (pin "8") (pinfunction "GNDIO_8") (pintype "bidirectional"))
      (node (ref "IC3") (pin "9") (pinfunction "GND_9") (pintype "bidirectional"))
      (node (ref "IC9") (pin "B1") (pinfunction "VSEL_B1") (pintype "bidirectional"))
      (node (ref "IC9") (pin "C1") (pinfunction "AGND_C1") (pintype "bidirectional"))
      (node (ref "IC9") (pin "C2") (pinfunction "PGND_1_C2") (pintype "bidirectional"))
      (node (ref "IC9") (pin "C3") (pinfunction "PGND_2_C3") (pintype "bidirectional"))
      (node (ref "J1") (pin "17") (pinfunction "17_17") (pintype "bidirectional"))
      (node (ref "J1") (pin "8") (pinfunction "8_8") (pintype "bidirectional"))
      (node (ref "J1") (pin "MP1") (pinfunction "MP1_MP1") (pintype "bidirectional"))
      (node (ref "J1") (pin "MP2") (pinfunction "MP2_MP2") (pintype "bidirectional"))
      (node (ref "J2") (pin "3") (pinfunction "3_3") (pintype "bidirectional"))
      (node (ref "J2") (pin "5") (pinfunction "5_5") (pintype "bidirectional"))
      (node (ref "J4") (pin "A12_B1") (pinfunction "GND_A12_B1") (pintype "power_in"))
      (node (ref "J4") (pin "A1_B12") (pinfunction "GND_A1_B12") (pintype "power_in"))
      (node (ref "J4") (pin "SH1") (pinfunction "SHIELD_SH1") (pintype "passive"))
      (node (ref "J4") (pin "SH2") (pinfunction "SHIELD_SH2") (pintype "passive"))
      (node (ref "J4") (pin "SH3") (pinfunction "SHIELD_SH3") (pintype "passive"))
      (node (ref "J4") (pin "SH4") (pinfunction "SHIELD_SH4") (pintype "passive"))
      (node (ref "R1_USB") (pin "1") (pinfunction "1_1") (pintype "bidirectional"))
      (node (ref "R2_EP_DR") (pin "1") (pinfunction "1_1") (pintype "bidirectional"))
      (node (ref "R2_USB") (pin "2") (pinfunction "2_2") (pintype "bidirectional"))
      (node (ref "R3") (pin "1") (pinfunction "1_1") (pintype "bidirectional"))
      (node (ref "R9") (pin "1") (pinfunction "1_1") (pintype "bidirectional"))
      (node (ref "R_TYPE_SEL") (pin "1") (pinfunction "1_1") (pintype "bidirectional"))
      (node (ref "SJ1") (pin "1") (pinfunction "1_1") (pintype "passive"))
      (node (ref "SW_DN") (pin "1") (pinfunction "1_1") (pintype "passive"))
      (node (ref "SW_ENT") (pin "1") (pinfunction "1_1") (pintype "passive"))
      (node (ref "SW_UP") (pin "1") (pinfunction "1_1") (pintype "passive"))
      (node (ref "TP2") (pin "TP") (pinfunction "TP_TP") (pintype "input"))
      (node (ref "TP_GND") (pin "TP") (pinfunction "TP_TP") (pintype "input"))
      (node (ref "U1") (pin "P$74") (pinfunction "VSS_PAD_P$74") (pintype "bidirectional"))
      (node (ref "U1") (pin "P$75") (pinfunction "VSS_PAD_P$75") (pintype "bidirectional"))
      (node (ref "U1") (pin "P$76") (pinfunction "VSS_PAD_P$76") (pintype "bidirectional"))
      (node (ref "U1") (pin "P$77") (pinfunction "VSS_PAD_P$77") (pintype "bidirectional"))
      (node (ref "U1") (pin "P$78") (pinfunction "VSS_PAD_P$78") (pintype "bidirectional"))
      (node (ref "U1") (pin "P$79") (pinfunction "VSS_PAD_P$79") (pintype "bidirectional"))
      (node (ref "U1") (pin "P$80") (pinfunction "VSS_PAD_P$80") (pintype "bidirectional"))
      (node (ref "U1") (pin "P$81") (pinfunction "VSS_PAD_P$81") (pintype "bidirectional"))
      (node (ref "U1") (pin "P$82") (pinfunction "VSS_PAD_P$82") (pintype "bidirectional"))
      (node (ref "U1") (pin "P$83") (pinfunction "VSS_PAD_P$83") (pintype "bidirectional"))
      (node (ref "U1") (pin "P$84") (pinfunction "VSS_PAD_P$84") (pintype "bidirectional"))
      (node (ref "U1") (pin "P$85") (pinfunction "VSS_PAD_P$85") (pintype "bidirectional"))
      (node (ref "U1") (pin "P$86") (pinfunction "VSS_PAD_P$86") (pintype "bidirectional"))
      (node (ref "U1") (pin "P$87") (pinfunction "VSS_PAD_P$87") (pintype "bidirectional"))
      (node (ref "U1") (pin "P$88") (pinfunction "VSS_PAD_P$88") (pintype "bidirectional"))
      (node (ref "U1") (pin "P$89") (pinfunction "VSS_PAD_P$89") (pintype "bidirectional"))
      (node (ref "U1") (pin "P$90") (pinfunction "VSS_PAD_P$90") (pintype "bidirectional"))
      (node (ref "U1") (pin "P$B7") (pinfunction "VSS_P$B7") (pintype "power_in"))
      (node (ref "U1") (pin "P$F23") (pinfunction "VSS_PA_P$F23") (pintype "bidirectional"))
      (node (ref "U3") (pin "1") (pinfunction "CTG_1") (pintype "power_in"))
      (node (ref "U3") (pin "4") (pinfunction "GND_4") (pintype "power_in"))
      (node (ref "U3") (pin "6") (pinfunction "QSTRT_6") (pintype "input"))
      (node (ref "U3") (pin "9") (pinfunction "EP_9") (pintype "power_in"))
      (node (ref "X1") (pin "2") (pinfunction "2_2") (pintype "passive"))
      (node (ref "X1") (pin "4") (pinfunction "4_4") (pintype "passive"))
    )
    (net (code "28") (name "HAPTIC_EN{slash}1.4C") (class "Default")
      (node (ref "IC2") (pin "A1") (pinfunction "EN_A1") (pintype "bidirectional"))
    )
    (net (code "29") (name "HAPTIC_EN{slash}2.6A") (class "Default")
      (node (ref "U1") (pin "P$U1") (pinfunction "P0.12_P$U1") (pintype "bidirectional"))
    )
    (net (code "30") (name "IMU_INT1") (class "Default")
      (node (ref "IC3") (pin "5") (pinfunction "INT1_5") (pintype "bidirectional"))
      (node (ref "U1") (pin "P$N1") (pinfunction "P0.08_P$N1") (pintype "bidirectional"))
    )
    (net (code "31") (name "IMU_INT2") (class "Default")
      (node (ref "IC3") (pin "6") (pinfunction "INT2_6") (pintype "bidirectional"))
      (node (ref "U1") (pin "P$P2") (pinfunction "P1.08_P$P2") (pintype "bidirectional"))
    )
    (net (code "32") (name "LX1") (class "Default")
      (node (ref "IC9") (pin "B2") (pinfunction "SW1_1_B2") (pintype "bidirectional"))
      (node (ref "IC9") (pin "B3") (pinfunction "SW1_2_B3") (pintype "bidirectional"))
      (node (ref "L7") (pin "1") (pinfunction "1_1") (pintype "bidirectional"))
    )
    (net (code "33") (name "LX2") (class "Default")
      (node (ref "IC9") (pin "D2") (pinfunction "SW2_1_D2") (pintype "bidirectional"))
      (node (ref "IC9") (pin "D3") (pinfunction "SW2_2_D3") (pintype "bidirectional"))
      (node (ref "L7") (pin "2") (pinfunction "2_2") (pintype "bidirectional"))
    )
    (net (code "34") (name "MOSI{slash}1.5B") (class "Default")
      (node (ref "J1") (pin "14") (pinfunction "14_14") (pintype "bidirectional"))
    )
    (net (code "35") (name "MOSI{slash}2.2D") (class "Default")
      (node (ref "U1") (pin "P$B13") (pinfunction "P0.03/AIN1_P$B13") (pintype "bidirectional"))
    )
    (net (code "36") (name "N$3") (class "Default")
      (node (ref "Q3") (pin "1") (pinfunction "G_1") (pintype "bidirectional"))
      (node (ref "R2_EP_DR") (pin "2") (pinfunction "2_2") (pintype "bidirectional"))
    )
    (net (code "37") (name "N$5") (class "Default")
      (node (ref "C42") (pin "1") (pinfunction "1_1") (pintype "passive"))
      (node (ref "C43") (pin "1") (pinfunction "1_1") (pintype "passive"))
    )
    (net (code "38") (name "Net-(D2-K)") (class "Default")
      (node (ref "C2-EP-DR") (pin "1") (pinfunction "1_1") (pintype "passive"))
      (node (ref "D2") (pin "1") (pinfunction "K_1") (pintype "bidirectional"))
      (node (ref "D4") (pin "2") (pinfunction "A_2") (pintype "bidirectional"))
    )
    (net (code "39") (name "Net-(D5-A)") (class "Default")
      (node (ref "C2-EP-DR") (pin "2") (pinfunction "2_2") (pintype "passive"))
      (node (ref "D5") (pin "2") (pinfunction "A_2") (pintype "bidirectional"))
      (node (ref "L5") (pin "1") (pinfunction "1_1") (pintype "passive"))
      (node (ref "Q3") (pin "3") (pinfunction "D_3") (pintype "bidirectional"))
    )
    (net (code "40") (name "Net-(EPD_C1-Pad2)") (class "Default")
      (node (ref "EPD_C1") (pin "2") (pinfunction "2_2") (pintype "passive"))
      (node (ref "J1") (pin "5") (pinfunction "5_5") (pintype "bidirectional"))
    )
    (net (code "41") (name "Net-(EPD_C2-Pad2)") (class "Default")
      (node (ref "EPD_C2") (pin "2") (pinfunction "2_2") (pintype "passive"))
      (node (ref "J1") (pin "4") (pinfunction "4_4") (pintype "bidirectional"))
    )
    (net (code "42") (name "Net-(EPD_C6-Pad2)") (class "Default")
      (node (ref "EPD_C6") (pin "2") (pinfunction "2_2") (pintype "passive"))
      (node (ref "J1") (pin "18") (pinfunction "18_18") (pintype "bidirectional"))
    )
    (net (code "43") (name "Net-(EPD_C7-Pad2)") (class "Default")
      (node (ref "EPD_C7") (pin "2") (pinfunction "2_2") (pintype "passive"))
      (node (ref "J1") (pin "19") (pinfunction "19_19") (pintype "bidirectional"))
    )
    (net (code "44") (name "Net-(EPD_C8-Pad2)") (class "Default")
      (node (ref "EPD_C8") (pin "2") (pinfunction "2_2") (pintype "passive"))
      (node (ref "J1") (pin "20") (pinfunction "20_20") (pintype "bidirectional"))
    )
    (net (code "45") (name "Net-(EPD_C10-Pad2)") (class "Default")
      (node (ref "EPD_C10") (pin "2") (pinfunction "2_2") (pintype "passive"))
      (node (ref "J1") (pin "22") (pinfunction "22_22") (pintype "bidirectional"))
    )
    (net (code "46") (name "Net-(EPD_C12-Pad2)") (class "Default")
      (node (ref "EPD_C12") (pin "2") (pinfunction "2_2") (pintype "passive"))
      (node (ref "J1") (pin "24") (pinfunction "24_24") (pintype "bidirectional"))
    )
    (net (code "47") (name "Net-(IC1-TS{slash}MR)") (class "Default")
      (node (ref "IC1") (pin "D1") (pinfunction "TS/MR_D1") (pintype "bidirectional"))
      (node (ref "R9") (pin "2") (pinfunction "2_2") (pintype "bidirectional"))
    )
    (net (code "48") (name "Net-(IC2-REG)") (class "Default")
      (node (ref "C32") (pin "2") (pinfunction "2_2") (pintype "passive"))
      (node (ref "IC2") (pin "A2") (pinfunction "REG_A2") (pintype "bidirectional"))
    )
    (net (code "49") (name "Net-(IC3-SDO)") (class "Default")
      (node (ref "IC3") (pin "1") (pinfunction "SDO_1") (pintype "bidirectional"))
      (node (ref "R3") (pin "2") (pinfunction "2_2") (pintype "bidirectional"))
    )
    (net (code "50") (name "Net-(IC9-SCL)") (class "Default")
      (node (ref "IC9") (pin "D1") (pinfunction "SCL_D1") (pintype "bidirectional"))
      (node (ref "R4") (pin "2") (pinfunction "2_2") (pintype "bidirectional"))
    )
    (net (code "51") (name "Net-(IC9-SDA)") (class "Default")
      (node (ref "IC9") (pin "E1") (pinfunction "SDA_E1") (pintype "bidirectional"))
      (node (ref "R2") (pin "2") (pinfunction "2_2") (pintype "bidirectional"))
    )
    (net (code "52") (name "Net-(J4-CC1)") (class "Default")
      (node (ref "J4") (pin "A5") (pinfunction "CC1_A5") (pintype "bidirectional"))
      (node (ref "R1_USB") (pin "2") (pinfunction "2_2") (pintype "bidirectional"))
    )
    (net (code "53") (name "Net-(J4-CC2)") (class "Default")
      (node (ref "J4") (pin "B5") (pinfunction "CC2_B5") (pintype "bidirectional"))
      (node (ref "R2_USB") (pin "1") (pinfunction "1_1") (pintype "bidirectional"))
    )
    (net (code "54") (name "Net-(L2-Pad2)") (class "Default")
      (node (ref "L2") (pin "2") (pinfunction "2_2") (pintype "passive"))
      (node (ref "L3") (pin "1") (pinfunction "1_1") (pintype "passive"))
    )
    (net (code "55") (name "Net-(R1_EP_DR-Pad1)") (class "Default")
      (node (ref "R1_EP_DR") (pin "1") (pinfunction "1_1") (pintype "bidirectional"))
      (node (ref "R_TYPE_SEL") (pin "2") (pinfunction "2_2") (pintype "bidirectional"))
      (node (ref "SJ1") (pin "2") (pinfunction "2_2") (pintype "passive"))
    )
    (net (code "56") (name "Net-(U1-ANT)") (class "Default")
      (node (ref "C3") (pin "1") (pinfunction "1_1") (pintype "passive"))
      (node (ref "L1") (pin "1") (pinfunction "1_1") (pintype "passive"))
      (node (ref "U1") (pin "P$H23") (pinfunction "ANT_P$H23") (pintype "bidirectional"))
    )
    (net (code "57") (name "Net-(U1-DCC)") (class "Default")
      (node (ref "L2") (pin "1") (pinfunction "1_1") (pintype "passive"))
      (node (ref "U1") (pin "P$B3") (pinfunction "DCC_P$B3") (pintype "output"))
    )
    (net (code "58") (name "Net-(U1-DEC2)") (class "Default")
      (node (ref "C13") (pin "1") (pinfunction "1_1") (pintype "passive"))
      (node (ref "U1") (pin "P$A18") (pinfunction "DEC2_P$A18") (pintype "bidirectional"))
    )
    (net (code "59") (name "Net-(U1-DEC3V3)") (class "Default")
      (node (ref "C20") (pin "1") (pinfunction "1_1") (pintype "passive"))
      (node (ref "U1") (pin "P$AC5") (pinfunction "DEC3V3_P$AC5") (pintype "bidirectional"))
    )
    (net (code "60") (name "Net-(U1-DEC5)") (class "Default")
      (node (ref "C9") (pin "1") (pinfunction "1_1") (pintype "passive"))
      (node (ref "U1") (pin "P$N24") (pinfunction "DEC5_P$N24") (pintype "bidirectional"))
    )
    (net (code "61") (name "Net-(U1-XC1)") (class "Default")
      (node (ref "C1") (pin "1") (pinfunction "1_1") (pintype "passive"))
      (node (ref "U1") (pin "P$B24") (pinfunction "XC1_P$B24") (pintype "input"))
      (node (ref "X1") (pin "1") (pinfunction "1_1") (pintype "passive"))
    )
    (net (code "62") (name "Net-(U1-XC2)") (class "Default")
      (node (ref "C2") (pin "1") (pinfunction "1_1") (pintype "passive"))
      (node (ref "U1") (pin "P$A23") (pinfunction "XC2_P$A23") (pintype "output"))
      (node (ref "X1") (pin "3") (pinfunction "3_3") (pintype "passive"))
    )
    (net (code "63") (name "OUT+") (class "Default")
      (node (ref "IC2") (pin "A3") (pinfunction "OUT+_A3") (pintype "bidirectional"))
      (node (ref "TP_OP") (pin "TP") (pinfunction "TP_TP") (pintype "input"))
    )
    (net (code "64") (name "OUT-") (class "Default")
      (node (ref "IC2") (pin "C3") (pinfunction "OUT-_C3") (pintype "bidirectional"))
      (node (ref "TP_ON") (pin "TP") (pinfunction "TP_TP") (pintype "input"))
    )
    (net (code "65") (name "P0.04") (class "Default")
      (node (ref "U1") (pin "P$J1") (pinfunction "P0.04/AIN2_P$J1") (pintype "bidirectional"))
    )
    (net (code "66") (name "P0.13{slash}1.5D") (class "Default")
      (node (ref "C30") (pin "2") (pinfunction "2_2") (pintype "passive"))
      (node (ref "R5") (pin "1") (pinfunction "1_1") (pintype "bidirectional"))
      (node (ref "SW_UP") (pin "2") (pinfunction "2_2") (pintype "passive"))
    )
    (net (code "67") (name "P0.13{slash}2.6C") (class "Default")
      (node (ref "U1") (pin "P$AD8") (pinfunction "P0.13_P$AD8") (pintype "bidirectional"))
    )
    (net (code "68") (name "P0.14{slash}1.5D") (class "Default")
      (node (ref "C31") (pin "2") (pinfunction "2_2") (pintype "passive"))
      (node (ref "R8") (pin "1") (pinfunction "1_1") (pintype "bidirectional"))
      (node (ref "SW_ENT") (pin "2") (pinfunction "2_2") (pintype "passive"))
    )
    (net (code "69") (name "P0.14{slash}2.7C") (class "Default")
      (node (ref "U1") (pin "P$AC9") (pinfunction "P0.14_P$AC9") (pintype "bidirectional"))
    )
    (net (code "70") (name "P0.19") (class "Default")
      (node (ref "U1") (pin "P$AC15") (pinfunction "P0.19_P$AC15") (pintype "bidirectional"))
    )
    (net (code "71") (name "P0.20") (class "Default")
      (node (ref "U1") (pin "P$AD16") (pinfunction "P0.20_P$AD16") (pintype "bidirectional"))
    )
    (net (code "72") (name "P0.21") (class "Default")
      (node (ref "U1") (pin "P$AC17") (pinfunction "P0.21_P$AC17") (pintype "bidirectional"))
    )
    (net (code "73") (name "P0.22") (class "Default")
      (node (ref "U1") (pin "P$AD18") (pinfunction "P0.22_P$AD18") (pintype "bidirectional"))
    )
    (net (code "74") (name "P0.23") (class "Default")
      (node (ref "U1") (pin "P$AC19") (pinfunction "P0.23_P$AC19") (pintype "bidirectional"))
    )
    (net (code "75") (name "P0.24") (class "Default")
      (node (ref "U1") (pin "P$AD20") (pinfunction "P0.24_P$AD20") (pintype "bidirectional"))
    )
    (net (code "76") (name "P0.25") (class "Default")
      (node (ref "U1") (pin "P$AC21") (pinfunction "P0.25_P$AC21") (pintype "bidirectional"))
    )
    (net (code "77") (name "P0.26") (class "Default")
      (node (ref "U1") (pin "P$G1") (pinfunction "P0.26_P$G1") (pintype "bidirectional"))
    )
    (net (code "78") (name "P0.27") (class "Default")
      (node (ref "U1") (pin "P$H2") (pinfunction "P0.27_P$H2") (pintype "bidirectional"))
    )
    (net (code "79") (name "P0.28") (class "Default")
      (node (ref "U1") (pin "P$B11") (pinfunction "P0.28/AIN4_P$B11") (pintype "bidirectional"))
    )
    (net (code "80") (name "P0.29") (class "Default")
      (node (ref "U1") (pin "P$A10") (pinfunction "P0.29/AIN5_P$A10") (pintype "bidirectional"))
    )
    (net (code "81") (name "P0.30") (class "Default")
      (node (ref "U1") (pin "P$B9") (pinfunction "P0.30/AIN6_P$B9") (pintype "bidirectional"))
    )
    (net (code "82") (name "P0.31") (class "Default")
      (node (ref "U1") (pin "P$A8") (pinfunction "P0.31/AIN7_P$A8") (pintype "bidirectional"))
    )
    (net (code "83") (name "P1.01{slash}1.6C") (class "Default")
      (node (ref "DMG2305UX-7") (pin "1") (pinfunction "G_1") (pintype "bidirectional"))
      (node (ref "R_PWR_EPD") (pin "1") (pinfunction "1_1") (pintype "passive"))
    )
    (net (code "84") (name "P1.01{slash}2.4B") (class "Default")
      (node (ref "U1") (pin "P$Y23") (pinfunction "P1.01_P$Y23") (pintype "bidirectional"))
    )
    (net (code "85") (name "P1.02{slash}1.6C") (class "Default")
      (node (ref "C29") (pin "2") (pinfunction "2_2") (pintype "passive"))
      (node (ref "R7") (pin "1") (pinfunction "1_1") (pintype "bidirectional"))
      (node (ref "SW_DN") (pin "2") (pinfunction "2_2") (pintype "passive"))
    )
    (net (code "86") (name "P1.02{slash}2.8C") (class "Default")
      (node (ref "U1") (pin "P$W24") (pinfunction "P1.02_P$W24") (pintype "bidirectional"))
    )
    (net (code "87") (name "P1.03") (class "Default")
      (node (ref "U1") (pin "P$V23") (pinfunction "P1.03_P$V23") (pintype "bidirectional"))
    )
    (net (code "88") (name "P1.04") (class "Default")
      (node (ref "U1") (pin "P$U24") (pinfunction "P1.04_P$U24") (pintype "bidirectional"))
    )
    (net (code "89") (name "P1.05") (class "Default")
      (node (ref "U1") (pin "P$T23") (pinfunction "P1.05_P$T23") (pintype "bidirectional"))
    )
    (net (code "90") (name "P1.06") (class "Default")
      (node (ref "U1") (pin "P$R24") (pinfunction "P1.06_P$R24") (pintype "bidirectional"))
    )
    (net (code "91") (name "P1.07") (class "Default")
      (node (ref "U1") (pin "P$P23") (pinfunction "P1.07_P$P23") (pintype "bidirectional"))
    )
    (net (code "92") (name "P1.09") (class "Default")
      (node (ref "U1") (pin "P$L24") (pinfunction "P0.09/NFC1_P$L24") (pintype "bidirectional"))
      (node (ref "U1") (pin "P$R1") (pinfunction "P1.09_P$R1") (pintype "bidirectional"))
    )
    (net (code "93") (name "P1.10") (class "Default")
      (node (ref "U1") (pin "P$A20") (pinfunction "P1.10_P$A20") (pintype "bidirectional"))
    )
    (net (code "94") (name "P1.11") (class "Default")
      (node (ref "U1") (pin "P$B19") (pinfunction "P1.11_P$B19") (pintype "bidirectional"))
    )
    (net (code "95") (name "P1.12") (class "Default")
      (node (ref "U1") (pin "P$B17") (pinfunction "P1.12_P$B17") (pintype "bidirectional"))
    )
    (net (code "96") (name "P1.13") (class "Default")
      (node (ref "U1") (pin "P$A16") (pinfunction "P1.13_P$A16") (pintype "bidirectional"))
    )
    (net (code "97") (name "P1.14") (class "Default")
      (node (ref "U1") (pin "P$B15") (pinfunction "P1.14_P$B15") (pintype "bidirectional"))
    )
    (net (code "98") (name "P1.15") (class "Default")
      (node (ref "U1") (pin "P$A14") (pinfunction "P1.15_P$A14") (pintype "bidirectional"))
    )
    (net (code "99") (name "PMIC_INT") (class "Default")
      (node (ref "IC1") (pin "A1") (pinfunction "~{INT}_A1") (pintype "bidirectional"))
      (node (ref "U1") (pin "P$T2") (pinfunction "P0.11_P$T2") (pintype "bidirectional"))
    )
    (net (code "100") (name "PREVGH") (class "Default")
      (node (ref "D5") (pin "1") (pinfunction "K_1") (pintype "bidirectional"))
      (node (ref "EPD_C9") (pin "2") (pinfunction "2_2") (pintype "passive"))
      (node (ref "J1") (pin "21") (pinfunction "21_21") (pintype "bidirectional"))
    )
    (net (code "101") (name "PREVGL") (class "Default")
      (node (ref "D2") (pin "2") (pinfunction "A_2") (pintype "bidirectional"))
      (node (ref "EPD_C11") (pin "2") (pinfunction "2_2") (pintype "passive"))
      (node (ref "J1") (pin "23") (pinfunction "23_23") (pintype "bidirectional"))
    )
    (net (code "102") (name "RESE") (class "Default")
      (node (ref "J1") (pin "3") (pinfunction "3_3") (pintype "bidirectional"))
      (node (ref "Q3") (pin "2") (pinfunction "S_2") (pintype "bidirectional"))
      (node (ref "R1_EP_DR") (pin "2") (pinfunction "2_2") (pintype "bidirectional"))
    )
    (net (code "103") (name "RESET") (class "Default")
      (node (ref "J2") (pin "6") (pinfunction "6_6") (pintype "bidirectional"))
      (node (ref "TP_RESET") (pin "TP") (pinfunction "TP_TP") (pintype "input"))
      (node (ref "U1") (pin "P$AC13") (pinfunction "P0.18/RESET_P$AC13") (pintype "bidirectional"))
    )
    (net (code "104") (name "SCK{slash}1.5B") (class "Default")
      (node (ref "J1") (pin "13") (pinfunction "13_13") (pintype "bidirectional"))
    )
    (net (code "105") (name "SCK{slash}2.2D") (class "Default")
      (node (ref "U1") (pin "P$A12") (pinfunction "P0.02/AIN0_P$A12") (pintype "bidirectional"))
    )
    (net (code "106") (name "SCL{slash}1.4C") (class "Default")
      (node (ref "IC2") (pin "C1") (pinfunction "SCL_C1") (pintype "bidirectional"))
      (node (ref "U3") (pin "7") (pinfunction "SCL_7") (pintype "input"))
    )
    (net (code "107") (name "SCL{slash}2.4C") (class "Default")
      (node (ref "IC1") (pin "B1") (pinfunction "SCL_B1") (pintype "bidirectional"))
      (node (ref "IC3") (pin "12") (pinfunction "SCX_12") (pintype "bidirectional"))
      (node (ref "R17") (pin "2") (pinfunction "2_2") (pintype "bidirectional"))
      (node (ref "R4") (pin "1") (pinfunction "1_1") (pintype "bidirectional"))
      (node (ref "TP_SCL") (pin "TP") (pinfunction "TP_TP") (pintype "input"))
      (node (ref "U1") (pin "P$M2") (pinfunction "P0.07_P$M2") (pintype "bidirectional"))
    )
    (net (code "108") (name "SDA{slash}1.4C") (class "Default")
      (node (ref "IC2") (pin "B2") (pinfunction "SDA_B2") (pintype "bidirectional"))
      (node (ref "U3") (pin "8") (pinfunction "SDA_8") (pintype "bidirectional"))
    )
    (net (code "109") (name "SDA{slash}2.4C") (class "Default")
      (node (ref "IC1") (pin "C1") (pinfunction "SDA_C1") (pintype "bidirectional"))
      (node (ref "IC3") (pin "2") (pinfunction "SDX_2") (pintype "bidirectional"))
      (node (ref "R18") (pin "2") (pinfunction "2_2") (pintype "bidirectional"))
      (node (ref "R2") (pin "1") (pinfunction "1_1") (pintype "bidirectional"))
      (node (ref "TP_SDA") (pin "TP") (pinfunction "TP_TP") (pintype "input"))
      (node (ref "U1") (pin "P$L1") (pinfunction "P0.06_P$L1") (pintype "bidirectional"))
    )
    (net (code "110") (name "SWDCLK") (class "Default")
      (node (ref "J2") (pin "4") (pinfunction "4_4") (pintype "bidirectional"))
      (node (ref "TP_SWDCLK") (pin "TP") (pinfunction "TP_TP") (pintype "input"))
      (node (ref "U1") (pin "P$AA24") (pinfunction "SWDCLK_P$AA24") (pintype "input"))
    )
    (net (code "111") (name "SWDIO") (class "Default")
      (node (ref "J2") (pin "2") (pinfunction "2_2") (pintype "bidirectional"))
      (node (ref "TP_SWDIO") (pin "TP") (pinfunction "TP_TP") (pintype "input"))
      (node (ref "U1") (pin "P$AC24") (pinfunction "SWDIO_P$AC24") (pintype "bidirectional"))
    )
    (net (code "112") (name "SWO") (class "Default")
      (node (ref "TP_SWO") (pin "TP") (pinfunction "TP_TP") (pintype "input"))
      (node (ref "U1") (pin "P$AD22") (pinfunction "P1.00_P$AD22") (pintype "bidirectional"))
    )
    (net (code "113") (name "VBAT{slash}1.2A") (class "Default")
      (node (ref "C27") (pin "2") (pinfunction "2_2") (pintype "passive"))
      (node (ref "TP1") (pin "TP") (pinfunction "TP_TP") (pintype "input"))
      (node (ref "U3") (pin "2") (pinfunction "CELL_2") (pintype "power_in"))
      (node (ref "U3") (pin "3") (pinfunction "VDD_3") (pintype "power_in"))
    )
    (net (code "114") (name "VBAT{slash}2.5C") (class "Default")
      (node (ref "C37") (pin "2") (pinfunction "2_2") (pintype "passive"))
      (node (ref "IC1") (pin "C2") (pinfunction "BAT_C2") (pintype "bidirectional"))
    )
    (net (code "115") (name "VBUS{slash}1.5D") (class "Default")
      (node (ref "D1") (pin "5") (pinfunction "VBUS_5") (pintype "bidirectional"))
      (node (ref "J4") (pin "A4_B9") (pinfunction "VBUS_A4_B9") (pintype "power_in"))
      (node (ref "J4") (pin "A9_B4") (pinfunction "VBUS_A9_B4") (pintype "power_in"))
    )
    (net (code "116") (name "VBUS{slash}2.6D") (class "Default")
      (node (ref "C21") (pin "1") (pinfunction "1_1") (pintype "passive"))
      (node (ref "C38") (pin "1") (pinfunction "1_1") (pintype "passive"))
      (node (ref "IC1") (pin "A2") (pinfunction "IN_A2") (pintype "bidirectional"))
      (node (ref "U1") (pin "P$AD2") (pinfunction "VBUS_P$AD2") (pintype "power_in"))
    )
    (net (code "117") (name "VREG") (class "Default")
      (node (ref "C23") (pin "1") (pinfunction "1_1") (pintype "passive"))
      (node (ref "C24") (pin "2") (pinfunction "2_2") (pintype "passive"))
      (node (ref "C39") (pin "1") (pinfunction "1_1") (pintype "passive"))
      (node (ref "IC1") (pin "B2") (pinfunction "SYS_B2") (pintype "bidirectional"))
      (node (ref "IC9") (pin "A1") (pinfunction "EN_A1") (pintype "bidirectional"))
      (node (ref "IC9") (pin "A2") (pinfunction "VIN_1_A2") (pintype "bidirectional"))
      (node (ref "IC9") (pin "A3") (pinfunction "VIN_2_A3") (pintype "bidirectional"))
      (node (ref "TP_VREG") (pin "TP") (pinfunction "TP_TP") (pintype "input"))
    )
    (net (code "118") (name "unconnected-(ANT1-NC-Pad2)") (class "Default")
      (node (ref "ANT1") (pin "2") (pinfunction "NC_2") (pintype "no_connect"))
    )
    (net (code "119") (name "unconnected-(IC3-ASCL-Pad11)") (class "Default")
      (node (ref "IC3") (pin "11") (pinfunction "ASCL_11") (pintype "bidirectional"))
    )
    (net (code "120") (name "unconnected-(IC3-ASDA-Pad4)") (class "Default")
      (node (ref "IC3") (pin "4") (pinfunction "ASDA_4") (pintype "bidirectional"))
    )
    (net (code "121") (name "unconnected-(J1-Pad1)") (class "Default")
      (node (ref "J1") (pin "1") (pinfunction "1_1") (pintype "bidirectional"))
    )
    (net (code "122") (name "unconnected-(J1-Pad6)") (class "Default")
      (node (ref "J1") (pin "6") (pinfunction "6_6") (pintype "bidirectional"))
    )
    (net (code "123") (name "unconnected-(J1-Pad7)") (class "Default")
      (node (ref "J1") (pin "7") (pinfunction "7_7") (pintype "bidirectional"))
    )
    (net (code "124") (name "unconnected-(J4-SBU1-PadA8)") (class "Default")
      (node (ref "J4") (pin "A8") (pinfunction "SBU1_A8") (pintype "bidirectional"))
    )
    (net (code "125") (name "unconnected-(J4-SBU2-PadB8)") (class "Default")
      (node (ref "J4") (pin "B8") (pinfunction "SBU2_B8") (pintype "bidirectional"))
    )
    (net (code "126") (name "unconnected-(U1-DCCH-PadP$AB2)") (class "Default")
      (node (ref "U1") (pin "P$AB2") (pinfunction "DCCH_P$AB2") (pintype "bidirectional"))
    )
  )
)
